# USB-UART.net
KiCad netlist of a schematic drawn in Altium Designer
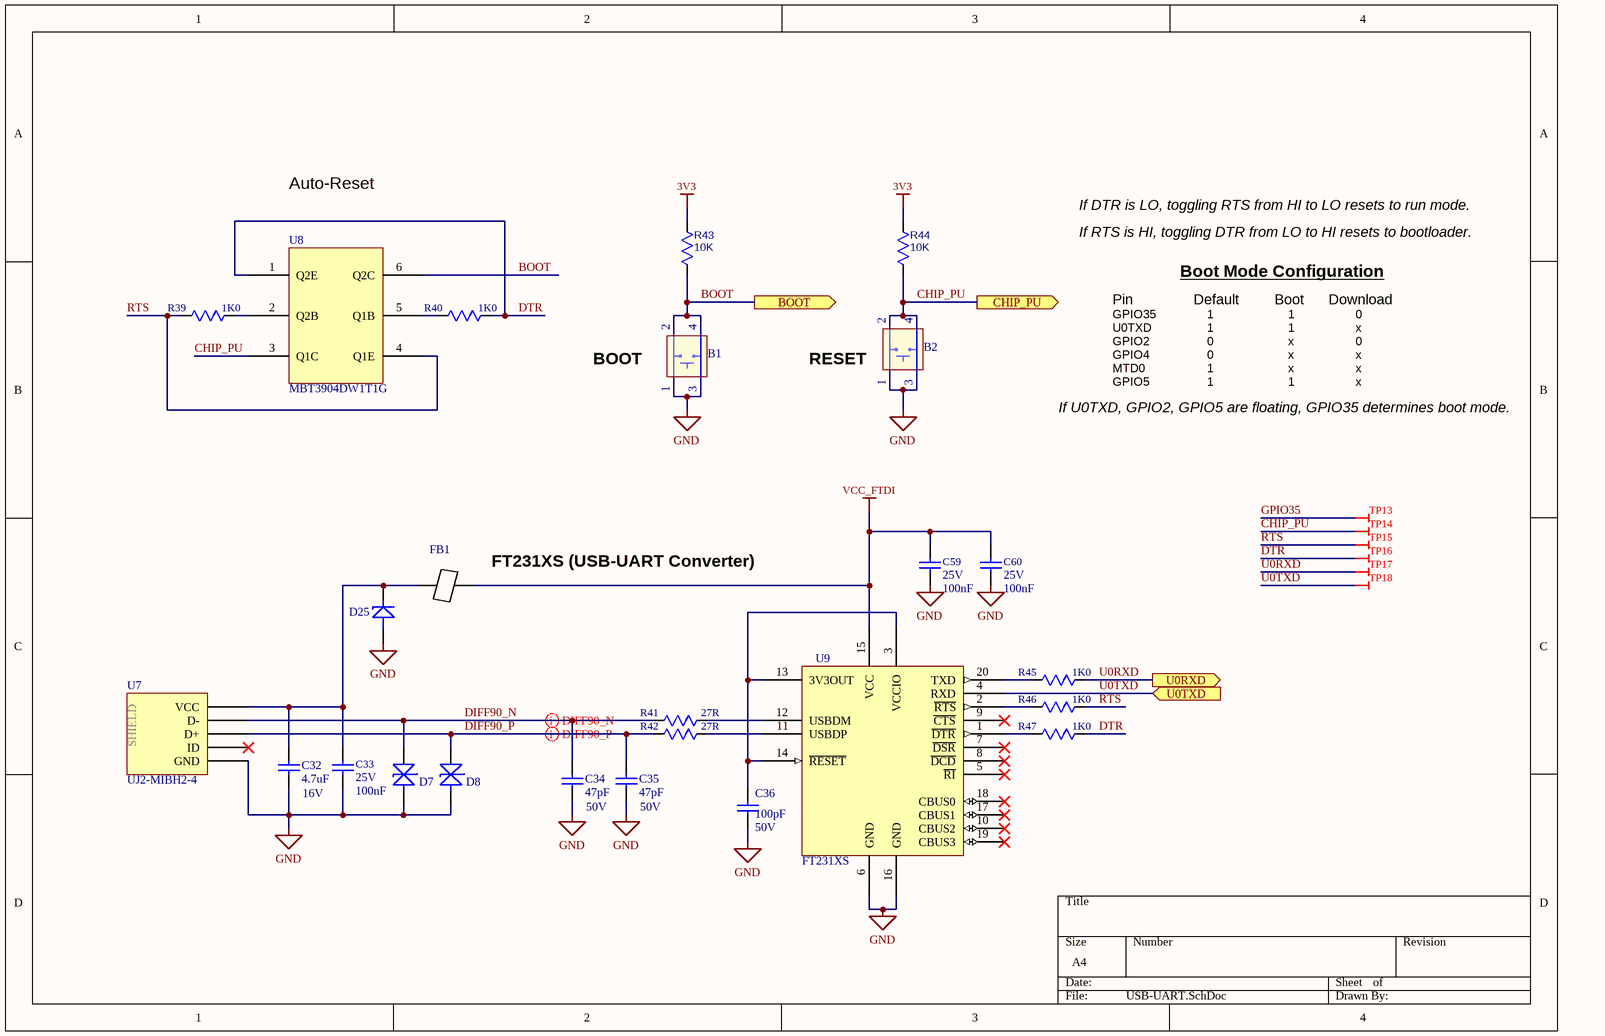
[diagram p0: USB-UART.SchDoc]

(export (version "E")
  (design (tool "Eeschema 10.0.6"))
  (components
    (comp (ref "B1")
      (value "Button C&K PTS815 SJG 250 SMTR LFS")
      (footprint "PTS 815")
      (description "Push Button Top")
      (fields
        (field (name "MANUFACTURER") "C&K Components")
        (field (name "MANUFACTURER PART NUMBER") "PTS815 SJG 250 SMTR LFS")
      )
      (libsource (lib "Connectors") (part "Button C&K PTS815 SJG 250 SMTR LFS"))
    )
    (comp (ref "B2")
      (value "Button C&K PTS815 SJG 250 SMTR LFS")
      (footprint "PTS 815")
      (description "Push Button Top")
      (fields
        (field (name "MANUFACTURER") "C&K Components")
        (field (name "MANUFACTURER PART NUMBER") "PTS815 SJG 250 SMTR LFS")
      )
      (libsource (lib "Connectors") (part "Button C&K PTS815 SJG 250 SMTR LFS"))
    )
    (comp (ref "C32")
      (value "4.7uF")
      (footprint "C1005[0402]")
      (description "Cap,4.7uF,10V,20%,X5R,0402")
      (fields
        (field (name "MANUFACTURER") "Samsung Electro-Mechanics")
        (field (name "MANUFACTURER PART NUMBER") "CL05A475MO5NUNC")
        (field (name "VOLTAGE") "16V")
      )
      (libsource (lib "Capacitors") (part "4.7uF_0402_10V"))
    )
    (comp (ref "C33")
      (value "100nF")
      (footprint "CAPC1005X06N")
      (fields
        (field (name "VOLTAGE") "25V")
        (field (name "MANUFACTURER PART NUMBER") "CL05A104KA5NNNC")
        (field (name "MANUFACTURER") "Samsung")
        (field (name "Comment") "4.7uF")
      )
      (libsource (lib "Capacitors") (part "4.7uF_0603_10V"))
    )
    (comp (ref "C34")
      (value "47pF")
      (footprint "C1005[0402]")
      (description "Cap,47pF,50V,5%,C0G/NP0")
      (fields
        (field (name "MANUFACTURER") "Yageo")
        (field (name "MANUFACTURER PART NUMBER") "CC0402JRNPO9BN470")
        (field (name "VOLTAGE") "50V")
      )
      (libsource (lib "Capacitors") (part "47pF_0402_50V"))
    )
    (comp (ref "C35")
      (value "47pF")
      (footprint "C1005[0402]")
      (description "Cap,47pF,50V,5%,C0G/NP0")
      (fields
        (field (name "MANUFACTURER PART NUMBER") "CC0402JRNPO9BN470")
        (field (name "MANUFACTURER") "Yageo")
        (field (name "VOLTAGE") "50V")
      )
      (libsource (lib "Capacitors") (part "47pF_0402_50V"))
    )
    (comp (ref "C36")
      (value "100pF")
      (footprint "C1005[0402]")
      (description "Cap,100pF,10V,5%,C0G/NP0,0402")
      (fields
        (field (name "MANUFACTURER PART NUMBER") "CC0402JRNPO9BN101")
        (field (name "MANUFACTURER") "Yageo")
        (field (name "VOLTAGE") "50V")
      )
      (libsource (lib "Capacitors") (part "100pF_0402_10V"))
    )
    (comp (ref "C59")
      (value "100nF")
      (footprint "CAPC1005X06N")
      (fields
        (field (name "VOLTAGE") "25V")
        (field (name "MANUFACTURER PART NUMBER") "CL05A104KA5NNNC")
        (field (name "MANUFACTURER") "Samsung")
        (field (name "Comment") "4.7uF")
      )
      (libsource (lib "Capacitors") (part "4.7uF_0603_10V"))
    )
    (comp (ref "C60")
      (value "100nF")
      (footprint "CAPC1005X06N")
      (fields
        (field (name "VOLTAGE") "25V")
        (field (name "MANUFACTURER PART NUMBER") "CL05A104KA5NNNC")
        (field (name "MANUFACTURER") "Samsung")
        (field (name "Comment") "4.7uF")
      )
      (libsource (lib "Capacitors") (part "4.7uF_0603_10V"))
    )
    (comp (ref "D7")
      (value "ESD7951ST5GOSCT-ND")
      (footprint "SODFL100X40-2N")
      (description "TVS Diode")
      (fields
        (field (name "MANUFACTURER") "ON Semiconductor")
        (field (name "MANUFACTURER PART NUMBER") "ESD7951ST5G")
      )
      (libsource (lib "Gas Monitor Components") (part "ESD7951S"))
    )
    (comp (ref "D8")
      (value "ESD7951ST5GOSCT-ND")
      (footprint "SODFL100X40-2N")
      (description "TVS Diode")
      (fields
        (field (name "MANUFACTURER") "ON Semiconductor")
        (field (name "MANUFACTURER PART NUMBER") "ESD7951ST5G")
      )
      (libsource (lib "Gas Monitor Components") (part "ESD7951S"))
    )
    (comp (ref "D25")
      (value "5V TVS")
      (footprint "NXP PTVSxS1UR-Series (SOD123W)")
      (fields
        (field (name "MANUFACTURER") "Nexperia")
        (field (name "MANUFACTURER PART NUMBER") "PTVS5V0S1UR,115")
      )
      (libsource (lib "FSM_2018") (part "NXP PTVSxS1UR-Series"))
    )
    (comp (ref "FB1")
      (value "Ferrite Bead")
      (footprint "MI0805K400R-10")
      (description "MI0805K400R-10")
      (fields (field (name "MANUFACTURER") "Laird"))
      (libsource (lib "Gas Monitor Components") (part "Ferrite Bead"))
    )
    (comp (ref "R39")
      (value "1K0")
      (footprint "RESC1005X03N")
      (description "RES 1K Ohm ±5%, 0.25W,1/4W 0603")
      (fields
        (field (name "MANUFACTURER") "Panasonic")
        (field (name "MANUFACTURER PART NUMBER") "ERJ-2RKF1001X")
      )
      (libsource (lib "Resistors") (part "1K00_0603_0.1W"))
    )
    (comp (ref "R40")
      (value "1K0")
      (footprint "RESC1005X03N")
      (description "RES 1K Ohm ±5%, 0.25W,1/4W 0603")
      (fields
        (field (name "MANUFACTURER") "Panasonic")
        (field (name "MANUFACTURER PART NUMBER") "ERJ-2RKF1001X")
      )
      (libsource (lib "Resistors") (part "1K00_0603_0.1W"))
    )
    (comp (ref "R41")
      (value "27R")
      (footprint "RESC1005X03N")
      (description "RES 1K Ohm ±5%, 0.25W,1/4W 0603")
      (fields
        (field (name "MANUFACTURER") "Panasonic")
        (field (name "MANUFACTURER PART NUMBER") "ERJ-2GEJ270X")
      )
      (libsource (lib "Resistors") (part "1K00_0603_0.1W"))
    )
    (comp (ref "R42")
      (value "27R")
      (footprint "RESC1005X03N")
      (description "RES 1K Ohm ±5%, 0.25W,1/4W 0603")
      (fields
        (field (name "MANUFACTURER") "Panasonic")
        (field (name "MANUFACTURER PART NUMBER") "ERJ-2GEJ270X")
      )
      (libsource (lib "Resistors") (part "1K00_0603_0.1W"))
    )
    (comp (ref "R43")
      (value "10K")
      (footprint "RESC1005X03N")
      (description "RES 1K Ohm ±5%, 0.25W,1/4W 0603")
      (fields
        (field (name "MANUFACTURER") "Panasonic")
        (field (name "MANUFACTURER PART NUMBER") "ERJ-2RKF1002X")
      )
      (libsource (lib "Resistors") (part "1K00_0603_0.1W"))
    )
    (comp (ref "R44")
      (value "10K")
      (footprint "RESC1005X03N")
      (description "RES 1K Ohm ±5%, 0.25W,1/4W 0603")
      (fields
        (field (name "MANUFACTURER") "Panasonic")
        (field (name "MANUFACTURER PART NUMBER") "ERJ-2RKF1002X")
      )
      (libsource (lib "Resistors") (part "1K00_0603_0.1W"))
    )
    (comp (ref "R45")
      (value "1K0")
      (footprint "RESC1005X03N")
      (description "RES 1K Ohm ±5%, 0.25W,1/4W 0603")
      (fields
        (field (name "MANUFACTURER") "Panasonic")
        (field (name "MANUFACTURER PART NUMBER") "ERJ-2RKF1001X")
      )
      (libsource (lib "Resistors") (part "1K00_0603_0.1W"))
    )
    (comp (ref "R46")
      (value "1K0")
      (footprint "RESC1005X03N")
      (description "RES 1K Ohm ±5%, 0.25W,1/4W 0603")
      (fields
        (field (name "MANUFACTURER") "Panasonic")
        (field (name "MANUFACTURER PART NUMBER") "ERJ-2RKF1001X")
      )
      (libsource (lib "Resistors") (part "1K00_0603_0.1W"))
    )
    (comp (ref "R47")
      (value "1K0")
      (footprint "RESC1005X03N")
      (description "RES 1K Ohm ±5%, 0.25W,1/4W 0603")
      (fields
        (field (name "MANUFACTURER") "Panasonic")
        (field (name "MANUFACTURER PART NUMBER") "ERJ-2RKF1001X")
      )
      (libsource (lib "Resistors") (part "1K00_0603_0.1W"))
    )
    (comp (ref "TP13")
      (value "PAD")
      (footprint "TP_SMD_39MIL")
      (description "SMD Test Pad")
      (fields (field (name "MANUFACTURER") "No P/N Required"))
      (libsource (lib "Connectors") (part "TP_SMD_39MIL"))
    )
    (comp (ref "TP14")
      (value "PAD")
      (footprint "TP_SMD_39MIL")
      (description "SMD Test Pad")
      (fields (field (name "MANUFACTURER") "No P/N Required"))
      (libsource (lib "Connectors") (part "TP_SMD_39MIL"))
    )
    (comp (ref "TP15")
      (value "PAD")
      (footprint "TP_SMD_39MIL")
      (description "SMD Test Pad")
      (fields (field (name "MANUFACTURER") "No P/N Required"))
      (libsource (lib "Connectors") (part "TP_SMD_39MIL"))
    )
    (comp (ref "TP16")
      (value "PAD")
      (footprint "TP_SMD_39MIL")
      (description "SMD Test Pad")
      (fields (field (name "MANUFACTURER") "No P/N Required"))
      (libsource (lib "Connectors") (part "TP_SMD_39MIL"))
    )
    (comp (ref "TP17")
      (value "PAD")
      (footprint "TP_SMD_39MIL")
      (description "SMD Test Pad")
      (fields (field (name "MANUFACTURER") "No P/N Required"))
      (libsource (lib "Connectors") (part "TP_SMD_39MIL"))
    )
    (comp (ref "TP18")
      (value "PAD")
      (footprint "TP_SMD_39MIL")
      (description "SMD Test Pad")
      (fields (field (name "MANUFACTURER") "No P/N Required"))
      (libsource (lib "Connectors") (part "TP_SMD_39MIL"))
    )
    (comp (ref "U7")
      (value "UJ2-MIBH2-4")
      (footprint "UJ2-MIBH2-4-SMT")
      (fields
        (field (name "MANUFACTURER") "CUI")
        (field (name "MANUFACTURER PART NUMBER") "UJ2-MIBH2-4-SMT-TR")
      )
      (libsource (lib "Gas Monitor Components") (part "USB Shield"))
    )
    (comp (ref "U8")
      (value "MBT3904DW1T1G")
      (footprint "SOT65P210X110-6N")
      (description "Dual NPN Transistors")
      (fields (field (name "MANUFACTURER") "ON Semiconductor"))
      (libsource (lib "Gas Monitor Components") (part "MBT3904DW1"))
    )
    (comp (ref "U9")
      (value "FT231XS")
      (footprint "SOP64P1030X175-20N")
      (description "USB-UART Interface")
      (fields (field (name "MANUFACTURER") "FTDI") (field (name "MANUFACTURER PART NUMBER") "FT231XS-R"))
      (libsource (lib "Gas Monitor Components") (part "FT231XS"))
    )
  )
  (nets
    (net (code "1") (name "/BOOT") (class "Default")
      (node (ref "B1") (pin "2") (pinfunction "2_2") (pintype "passive"))
      (node (ref "B1") (pin "4") (pinfunction "4_4") (pintype "passive"))
      (node (ref "R43") (pin "1") (pintype "passive"))
      (node (ref "U8") (pin "6") (pinfunction "Q2C_6") (pintype "passive"))
    )
    (net (code "2") (name "/CHIP_PU") (class "Default")
      (node (ref "B2") (pin "2") (pinfunction "2_2") (pintype "passive"))
      (node (ref "B2") (pin "4") (pinfunction "4_4") (pintype "passive"))
      (node (ref "R44") (pin "1") (pintype "passive"))
      (node (ref "TP14") (pin "1") (pintype "passive"))
      (node (ref "U8") (pin "3") (pinfunction "Q1C_3") (pintype "passive"))
    )
    (net (code "3") (name "/DIFF90_N") (class "Default")
      (node (ref "C34") (pin "2") (pintype "passive"))
      (node (ref "D7") (pin "2") (pinfunction "ANODE_2") (pintype "passive"))
      (node (ref "R41") (pin "2") (pintype "passive"))
      (node (ref "U7") (pin "2") (pinfunction "D-_2") (pintype "passive"))
    )
    (net (code "4") (name "/DIFF90_P") (class "Default")
      (node (ref "C35") (pin "2") (pintype "passive"))
      (node (ref "D8") (pin "2") (pinfunction "ANODE_2") (pintype "passive"))
      (node (ref "R42") (pin "2") (pintype "passive"))
      (node (ref "U7") (pin "3") (pinfunction "D+_3") (pintype "passive"))
    )
    (net (code "5") (name "/DTR") (class "Default")
      (node (ref "R40") (pin "2") (pintype "passive"))
      (node (ref "R47") (pin "2") (pintype "passive"))
      (node (ref "TP16") (pin "1") (pintype "passive"))
      (node (ref "U8") (pin "1") (pinfunction "Q2E_1") (pintype "passive"))
    )
    (net (code "6") (name "/GPIO35") (class "Default") (node (ref "TP13") (pin "1") (pintype "passive")))
    (net (code "7") (name "/RTS") (class "Default")
      (node (ref "R39") (pin "1") (pintype "passive"))
      (node (ref "R46") (pin "2") (pintype "passive"))
      (node (ref "TP15") (pin "1") (pintype "passive"))
      (node (ref "U8") (pin "4") (pinfunction "Q1E_4") (pintype "passive"))
    )
    (net (code "8") (name "/U0RXD") (class "Default")
      (node (ref "R45") (pin "2") (pintype "passive"))
      (node (ref "TP17") (pin "1") (pintype "passive"))
    )
    (net (code "9") (name "/U0TXD") (class "Default")
      (node (ref "TP18") (pin "1") (pintype "passive"))
      (node (ref "U9") (pin "4") (pinfunction "RXD_4") (pintype "passive"))
    )
    (net (code "10") (name "3V3") (class "Default")
      (node (ref "R43") (pin "2") (pintype "passive"))
      (node (ref "R44") (pin "2") (pintype "passive"))
    )
    (net (code "11") (name "GND") (class "Default")
      (node (ref "B1") (pin "1") (pinfunction "1_1") (pintype "passive"))
      (node (ref "B1") (pin "3") (pinfunction "3_3") (pintype "passive"))
      (node (ref "B2") (pin "1") (pinfunction "1_1") (pintype "passive"))
      (node (ref "B2") (pin "3") (pinfunction "3_3") (pintype "passive"))
      (node (ref "C32") (pin "1") (pintype "passive"))
      (node (ref "C33") (pin "2") (pintype "passive"))
      (node (ref "C34") (pin "1") (pintype "passive"))
      (node (ref "C35") (pin "1") (pintype "passive"))
      (node (ref "C36") (pin "1") (pintype "passive"))
      (node (ref "C59") (pin "2") (pintype "passive"))
      (node (ref "C60") (pin "2") (pintype "passive"))
      (node (ref "D25") (pin "2") (pinfunction "2_2") (pintype "passive"))
      (node (ref "D7") (pin "1") (pinfunction "CATHODE_1") (pintype "passive"))
      (node (ref "D8") (pin "1") (pinfunction "CATHODE_1") (pintype "passive"))
      (node (ref "U7") (pin "5") (pinfunction "GND_5") (pintype "power_in"))
      (node (ref "U9") (pin "16") (pinfunction "GND_16") (pintype "power_in"))
      (node (ref "U9") (pin "6") (pinfunction "GND_6") (pintype "power_in"))
    )
    (net (code "12") (name "Net-(U7-VCC)") (class "Default")
      (node (ref "C32") (pin "2") (pintype "passive"))
      (node (ref "C33") (pin "1") (pintype "passive"))
      (node (ref "D25") (pin "1") (pinfunction "1_1") (pintype "passive"))
      (node (ref "FB1") (pin "1") (pinfunction "1_1") (pintype "passive"))
      (node (ref "U7") (pin "1") (pinfunction "VCC_1") (pintype "power_in"))
    )
    (net (code "13") (name "Net-(U8-Q1B)") (class "Default")
      (node (ref "R40") (pin "1") (pintype "passive"))
      (node (ref "U8") (pin "5") (pinfunction "Q1B_5") (pintype "passive"))
    )
    (net (code "14") (name "Net-(U8-Q2B)") (class "Default")
      (node (ref "R39") (pin "2") (pintype "passive"))
      (node (ref "U8") (pin "2") (pinfunction "Q2B_2") (pintype "passive"))
    )
    (net (code "15") (name "Net-(U9-3V3OUT)") (class "Default")
      (node (ref "C36") (pin "2") (pintype "passive"))
      (node (ref "U9") (pin "13") (pinfunction "3V3OUT_13") (pintype "power_in"))
      (node (ref "U9") (pin "14") (pinfunction "~{RESET}_14") (pintype "input"))
      (node (ref "U9") (pin "3") (pinfunction "VCCIO_3") (pintype "passive"))
    )
    (net (code "16") (name "Net-(U9-TXD)") (class "Default")
      (node (ref "R45") (pin "1") (pintype "passive"))
      (node (ref "U9") (pin "20") (pinfunction "TXD_20") (pintype "output"))
    )
    (net (code "17") (name "Net-(U9-USBDM)") (class "Default")
      (node (ref "R41") (pin "1") (pintype "passive"))
      (node (ref "U9") (pin "12") (pinfunction "USBDM_12") (pintype "passive"))
    )
    (net (code "18") (name "Net-(U9-USBDP)") (class "Default")
      (node (ref "R42") (pin "1") (pintype "passive"))
      (node (ref "U9") (pin "11") (pinfunction "USBDP_11") (pintype "passive"))
    )
    (net (code "19") (name "Net-(U9-~{DTR})") (class "Default")
      (node (ref "R47") (pin "1") (pintype "passive"))
      (node (ref "U9") (pin "1") (pinfunction "~{DTR}_1") (pintype "output"))
    )
    (net (code "20") (name "Net-(U9-~{RTS})") (class "Default")
      (node (ref "R46") (pin "1") (pintype "passive"))
      (node (ref "U9") (pin "2") (pinfunction "~{RTS}_2") (pintype "output"))
    )
    (net (code "21") (name "VCC_FTDI") (class "Default")
      (node (ref "C59") (pin "1") (pintype "passive"))
      (node (ref "C60") (pin "1") (pintype "passive"))
      (node (ref "FB1") (pin "2") (pinfunction "2_2") (pintype "passive"))
      (node (ref "U9") (pin "15") (pinfunction "VCC_15") (pintype "power_in"))
    )
    (net (code "22") (name "unconnected-(U7-ID-Pad4)") (class "Default")
      (node (ref "U7") (pin "4") (pinfunction "ID_4") (pintype "passive+no_connect"))
    )
    (net (code "23") (name "unconnected-(U9-CBUS0-Pad18)") (class "Default")
      (node (ref "U9") (pin "18") (pinfunction "CBUS0_18") (pintype "bidirectional+no_connect"))
    )
    (net (code "24") (name "unconnected-(U9-CBUS1-Pad17)") (class "Default")
      (node (ref "U9") (pin "17") (pinfunction "CBUS1_17") (pintype "bidirectional+no_connect"))
    )
    (net (code "25") (name "unconnected-(U9-CBUS2-Pad10)") (class "Default")
      (node (ref "U9") (pin "10") (pinfunction "CBUS2_10") (pintype "bidirectional+no_connect"))
    )
    (net (code "26") (name "unconnected-(U9-CBUS3-Pad19)") (class "Default")
      (node (ref "U9") (pin "19") (pinfunction "CBUS3_19") (pintype "bidirectional+no_connect"))
    )
    (net (code "27") (name "unconnected-(U9-~{CTS}-Pad9)") (class "Default")
      (node (ref "U9") (pin "9") (pinfunction "~{CTS}_9") (pintype "passive+no_connect"))
    )
    (net (code "28") (name "unconnected-(U9-~{DCD}-Pad8)") (class "Default")
      (node (ref "U9") (pin "8") (pinfunction "~{DCD}_8") (pintype "passive+no_connect"))
    )
    (net (code "29") (name "unconnected-(U9-~{DSR}-Pad7)") (class "Default")
      (node (ref "U9") (pin "7") (pinfunction "~{DSR}_7") (pintype "passive+no_connect"))
    )
    (net (code "30") (name "unconnected-(U9-~{RI}-Pad5)") (class "Default")
      (node (ref "U9") (pin "5") (pinfunction "~{RI}_5") (pintype "passive+no_connect"))
    )
  )
)
